# HV_Module_6W.net
KiCad netlist of a schematic drawn in Altium Designer
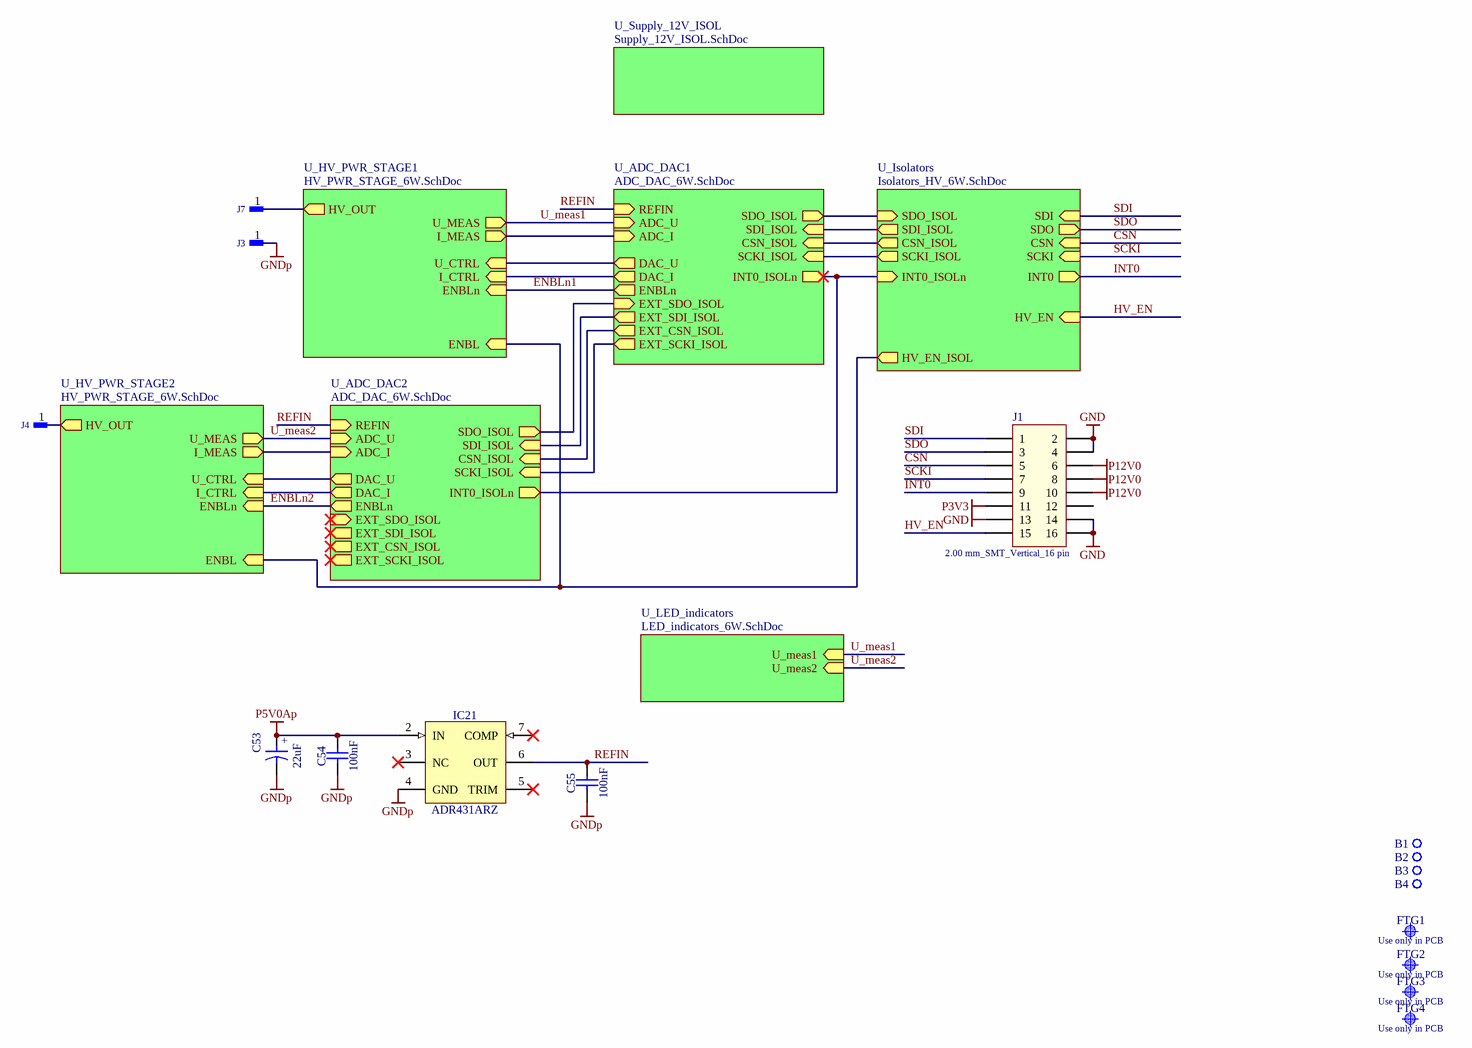
[diagram p0: HV_Module_6W.schdoc]

(export (version "E")
  (design (tool "Eeschema 10.0.6"))
  (components
    (comp (ref "B1")
      (value "Plated Hole")
      (footprint "MTG270_500")
      (description "Single Terminal Socket")
      (fields (field (name "PART NUMBER") "PLATED_HOLE2.7_PAD5.0") (field (name "AUTHOR") "CERN DEM JMW"))
      (libsource (lib "Eletro-mechanical") (part "Single Terminal Socket"))
    )
    (comp (ref "B2")
      (value "Plated Hole")
      (footprint "MTG270_500")
      (description "Single Terminal Socket")
      (fields (field (name "PART NUMBER") "PLATED_HOLE2.7_PAD5.0") (field (name "AUTHOR") "CERN DEM JMW"))
      (libsource (lib "Eletro-mechanical") (part "Single Terminal Socket"))
    )
    (comp (ref "B3")
      (value "Plated Hole")
      (footprint "MTG270_500")
      (description "Single Terminal Socket")
      (fields (field (name "PART NUMBER") "PLATED_HOLE2.7_PAD5.0") (field (name "AUTHOR") "CERN DEM JMW"))
      (libsource (lib "Eletro-mechanical") (part "Single Terminal Socket"))
    )
    (comp (ref "B4")
      (value "Plated Hole")
      (footprint "MTG270_500")
      (description "Single Terminal Socket")
      (fields (field (name "PART NUMBER") "PLATED_HOLE2.7_PAD5.0") (field (name "AUTHOR") "CERN DEM JMW"))
      (libsource (lib "Eletro-mechanical") (part "Single Terminal Socket"))
    )
    (comp (ref "C53")
      (value "22uF")
      (footprint "CAPMP3528X210N")
      (description "Polarised capacitor")
      (fields
        (field (name "PART NUMBER") "CTE3528-21_22UF_20V_10%")
        (field (name "VOLTAGE") "20V")
        (field (name "AUTHOR") "CERN DEM JLC")
      )
      (libsource (lib "Capacitors") (part "Capacitor - polarized"))
    )
    (comp (ref "C54")
      (value "100nF")
      (footprint "CAPC1005X55N")
      (description "Non-polarised capacitor")
      (fields
        (field (name "PART NUMBER") "CC0402_100NF_16V_10%_X7R")
        (field (name "VOLTAGE") "16V")
        (field (name "AUTHOR") "CERN DEM JLC")
      )
      (libsource (lib "Capacitors") (part "Capacitor - non polarized"))
    )
    (comp (ref "C55")
      (value "100nF")
      (footprint "CAPC1005X55N")
      (description "Non-polarised capacitor")
      (fields
        (field (name "PART NUMBER") "CC0402_100NF_16V_10%_X7R")
        (field (name "VOLTAGE") "16V")
        (field (name "AUTHOR") "CERN DEM JLC")
      )
      (libsource (lib "Capacitors") (part "Capacitor - non polarized"))
    )
    (comp (ref "FTG1")
      (value "Use only in PCB")
      (footprint "FIDUCIAL_TOP_C100-200")
      (description "Fiducial Target")
      (fields (field (name "PART NUMBER") "FIDUCIAL_TARGET_C100-200") (field (name "AUTHOR") "CERN DEM JLC"))
      (libsource (lib "Eletro-mechanical") (part "Fiducial Target"))
    )
    (comp (ref "FTG2")
      (value "Use only in PCB")
      (footprint "FIDUCIAL_TOP_S100-200")
      (description "Fiducial Target")
      (fields (field (name "PART NUMBER") "FIDUCIAL_TARGET_S100-200") (field (name "AUTHOR") "CERN DEM JLC"))
      (libsource (lib "Eletro-mechanical") (part "Fiducial Target"))
    )
    (comp (ref "FTG3")
      (value "Use only in PCB")
      (footprint "FIDUCIAL_TOP_S100-200")
      (description "Fiducial Target")
      (fields (field (name "PART NUMBER") "FIDUCIAL_TARGET_S100-200") (field (name "AUTHOR") "CERN DEM JLC"))
      (libsource (lib "Eletro-mechanical") (part "Fiducial Target"))
    )
    (comp (ref "FTG4")
      (value "Use only in PCB")
      (footprint "FIDUCIAL_TOP_S100-200")
      (description "Fiducial Target")
      (fields (field (name "PART NUMBER") "FIDUCIAL_TARGET_S100-200") (field (name "AUTHOR") "CERN DEM JLC"))
      (libsource (lib "Eletro-mechanical") (part "Fiducial Target"))
    )
    (comp (ref "IC21")
      (value "ADR431ARZ")
      (footprint "SOIC127P600X175-8N")
      (fields (field (name "MANUFACTURER") "ANALOG DEVICES") (field (name "AUTHOR") "CERN DEM JLC"))
      (libsource (lib "ICs And Semiconductors") (part "ADR431"))
    )
    (comp (ref "J1")
      (value "2.00 mm_SMT_Vertical_16 pin")
      (footprint "62131621821")
      (description "Socket Header WR-PHD, Pitch 2.00 mm, SMT, Vertical, dual row, 16 pin")
      (fields (field (name "PART NUMBER") "62131621821") (field (name "PUBLISHER") "Wurth Elektronik"))
      (libsource (lib "ALTIUM-PHD_2_0_SMT_DUAL_SOCKET_HEADER_LOW_PROFILE_REEL_6213XX21821-rev18a") (part "62131621821"))
    )
    (comp (ref "J3")
      (value "SMD Pad")
      (footprint "R400X300")
      (description "Single SMD Pad")
      (fields (field (name "PART NUMBER") "SMD_PAD_4X3MM") (field (name "AUTHOR") "CERN DEM JLC"))
      (libsource (lib "Eletro-mechanical") (part "Single SMD Pad"))
    )
    (comp (ref "J4")
      (value "SMD Pad")
      (footprint "R400X300")
      (description "Single SMD Pad")
      (fields (field (name "PART NUMBER") "SMD_PAD_4X3MM") (field (name "AUTHOR") "CERN DEM JLC"))
      (libsource (lib "Eletro-mechanical") (part "Single SMD Pad"))
    )
    (comp (ref "J7")
      (value "SMD Pad")
      (footprint "R400X300")
      (description "Single SMD Pad")
      (fields (field (name "PART NUMBER") "SMD_PAD_4X3MM") (field (name "AUTHOR") "CERN DEM JLC"))
      (libsource (lib "Eletro-mechanical") (part "Single SMD Pad"))
    )
  )
  (nets
    (net (code "1") (name "/CSN") (class "Default")
      (node (ref "J1") (pin "5") (pinfunction "5_5") (pintype "passive"))
    )
    (net (code "16") (name "/HV_EN") (class "Default")
      (node (ref "J1") (pin "15") (pinfunction "15_15") (pintype "passive"))
    )
    (net (code "18") (name "/HV_OUT") (class "Default")
      (node (ref "J7") (pin "1") (pinfunction "1_1") (pintype "bidirectional"))
    )
    (net (code "19") (name "/HV_OUT_1") (class "Default")
      (node (ref "J4") (pin "1") (pinfunction "1_1") (pintype "bidirectional"))
    )
    (net (code "20") (name "/INT0") (class "Default")
      (node (ref "J1") (pin "9") (pinfunction "9_9") (pintype "passive"))
    )
    (net (code "24") (name "/REFIN") (class "Default")
      (node (ref "C55") (pin "2") (pinfunction "2_2") (pintype "passive"))
      (node (ref "IC21") (pin "6") (pinfunction "OUT_6") (pintype "power_in"))
    )
    (net (code "25") (name "/SCKI") (class "Default")
      (node (ref "J1") (pin "7") (pinfunction "7_7") (pintype "passive"))
    )
    (net (code "27") (name "/SDI") (class "Default")
      (node (ref "J1") (pin "1") (pinfunction "1_1") (pintype "passive"))
    )
    (net (code "29") (name "/SDO") (class "Default")
      (node (ref "J1") (pin "3") (pinfunction "3_3") (pintype "passive"))
    )
    (net (code "34") (name "GND") (class "Default")
      (node (ref "J1") (pin "13") (pinfunction "13_13") (pintype "passive"))
      (node (ref "J1") (pin "14") (pinfunction "14_14") (pintype "passive"))
      (node (ref "J1") (pin "16") (pinfunction "16_16") (pintype "passive"))
      (node (ref "J1") (pin "2") (pinfunction "2_2") (pintype "passive"))
      (node (ref "J1") (pin "4") (pinfunction "4_4") (pintype "passive"))
    )
    (net (code "35") (name "GNDp") (class "Default")
      (node (ref "C53") (pin "2") (pinfunction "2_2") (pintype "passive"))
      (node (ref "C54") (pin "1") (pinfunction "1_1") (pintype "passive"))
      (node (ref "C55") (pin "1") (pinfunction "1_1") (pintype "passive"))
      (node (ref "IC21") (pin "4") (pinfunction "GND_4") (pintype "power_in"))
      (node (ref "J3") (pin "1") (pinfunction "1_1") (pintype "bidirectional"))
    )
    (net (code "36") (name "P3V3") (class "Default")
      (node (ref "J1") (pin "11") (pinfunction "11_11") (pintype "passive"))
    )
    (net (code "37") (name "P5V0Ap") (class "Default")
      (node (ref "C53") (pin "1") (pinfunction "1_1") (pintype "passive"))
      (node (ref "C54") (pin "2") (pinfunction "2_2") (pintype "passive"))
      (node (ref "IC21") (pin "2") (pinfunction "IN_2") (pintype "input"))
    )
    (net (code "38") (name "P12V0") (class "Default")
      (node (ref "J1") (pin "10") (pinfunction "10_10") (pintype "passive"))
      (node (ref "J1") (pin "6") (pinfunction "6_6") (pintype "passive"))
      (node (ref "J1") (pin "8") (pinfunction "8_8") (pintype "passive"))
    )
    (net (code "39") (name "unconnected-(B1-Pad1)") (class "Default")
      (node (ref "B1") (pin "1") (pinfunction "1_1") (pintype "bidirectional"))
    )
    (net (code "40") (name "unconnected-(B2-Pad1)") (class "Default")
      (node (ref "B2") (pin "1") (pinfunction "1_1") (pintype "bidirectional"))
    )
    (net (code "41") (name "unconnected-(B3-Pad1)") (class "Default")
      (node (ref "B3") (pin "1") (pinfunction "1_1") (pintype "bidirectional"))
    )
    (net (code "42") (name "unconnected-(B4-Pad1)") (class "Default")
      (node (ref "B4") (pin "1") (pinfunction "1_1") (pintype "bidirectional"))
    )
    (net (code "43") (name "unconnected-(IC21-COMP-Pad7)") (class "Default")
      (node (ref "IC21") (pin "7") (pinfunction "COMP_7") (pintype "input+no_connect"))
    )
    (net (code "44") (name "unconnected-(IC21-NC-Pad3)") (class "Default")
      (node (ref "IC21") (pin "3") (pinfunction "NC_3") (pintype "passive+no_connect"))
    )
    (net (code "45") (name "unconnected-(IC21-TRIM-Pad5)") (class "Default")
      (node (ref "IC21") (pin "5") (pinfunction "TRIM_5") (pintype "passive+no_connect"))
    )
    (net (code "46") (name "unconnected-(J1-Pad12)") (class "Default")
      (node (ref "J1") (pin "12") (pinfunction "12_12") (pintype "passive"))
    )
  )
)
